# US_EPS_BR.net
KiCad netlist of a schematic drawn in Altium Designer
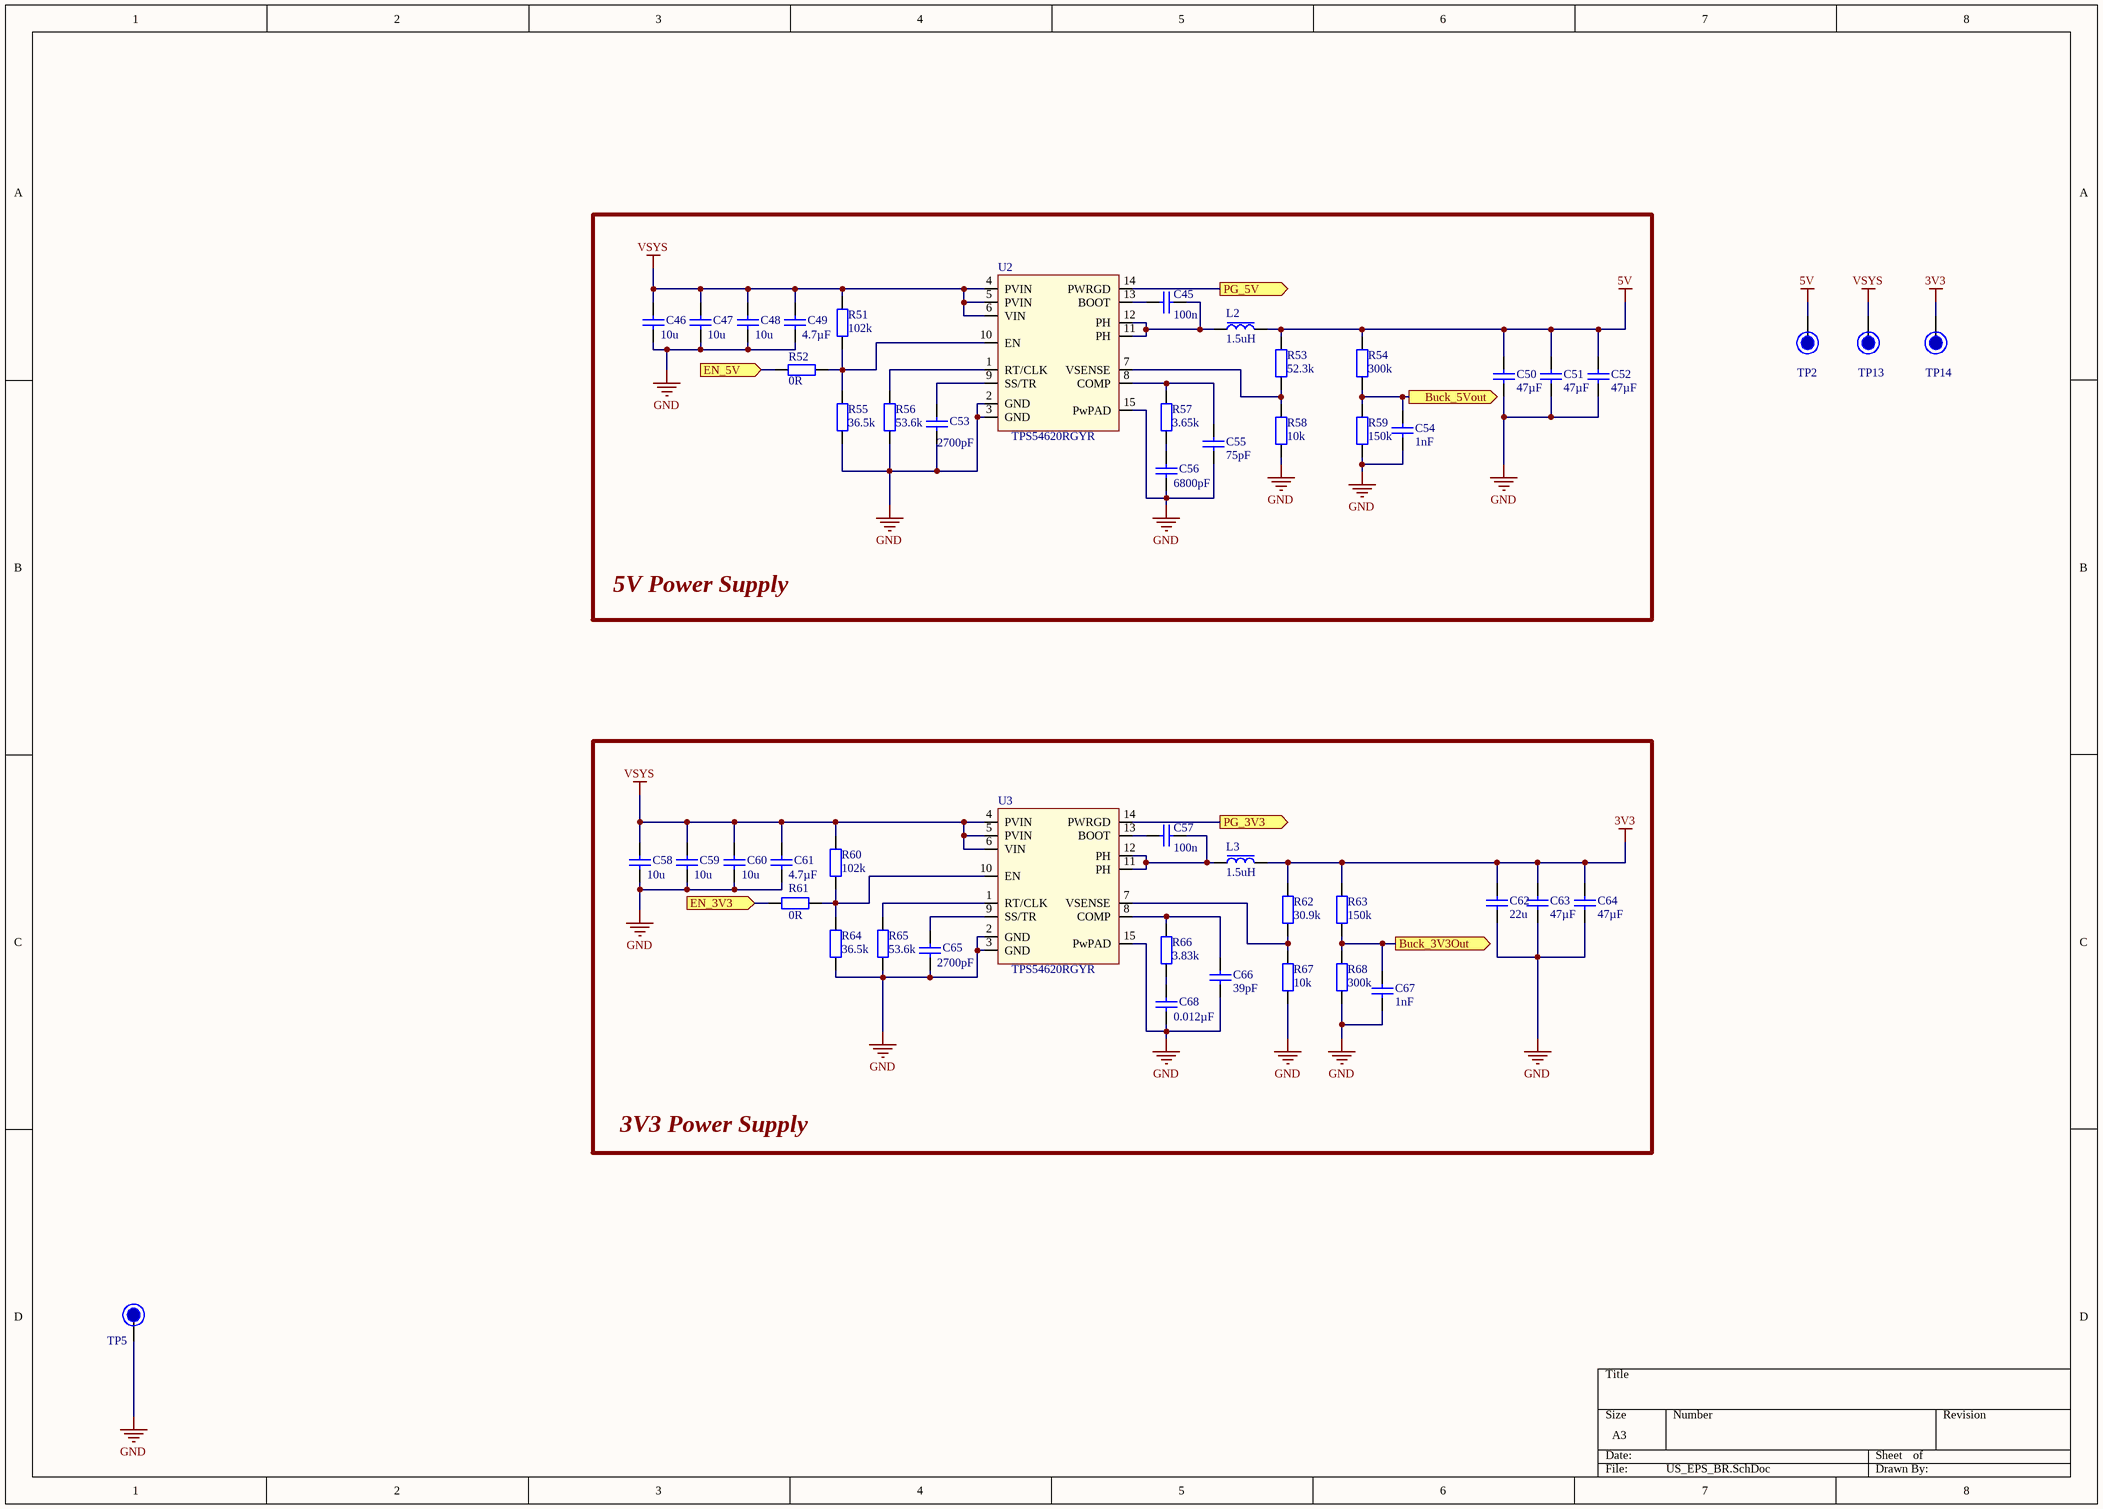
[diagram p0: US_EPS_BR.SchDoc]

(export (version "E")
  (design (tool "Eeschema 10.0.6"))
  (components
    (comp (ref "C45")
      (value "100n")
      (footprint "C0603_IPC_HD")
      (description "CAP CER 0.1UF 16V X7R 0603")
      (fields
        (field (name "MANUFACTURER") "Samsung Electro-Mechanics")
        (field (name "MANUFACTURER PART NUMBER") "CL10B104KO8NNNC")
      )
      (libsource (lib "alfasat_lib") (part "CL10B104KO8NNNC"))
    )
    (comp (ref "C46")
      (value "10u")
      (footprint "C0805_IPC_HD")
      (description "CAP CER 10UF 16V X7R 0805")
      (fields
        (field (name "MANUFACTURER") "Samsung Electro-Mechanics")
        (field (name "MANUFACTURER PART NUMBER") "CL21B106KOQNNNG")
      )
      (libsource (lib "alfasat_lib") (part "CL21B106KOQNNNG"))
    )
    (comp (ref "C47")
      (value "10u")
      (footprint "C0805_IPC_HD")
      (description "CAP CER 10UF 16V X7R 0805")
      (fields
        (field (name "MANUFACTURER") "Samsung Electro-Mechanics")
        (field (name "MANUFACTURER PART NUMBER") "CL21B106KOQNNNG")
      )
      (libsource (lib "alfasat_lib") (part "CL21B106KOQNNNG"))
    )
    (comp (ref "C48")
      (value "10u")
      (footprint "C0805_IPC_HD")
      (description "CAP CER 10UF 16V X7R 0805")
      (fields
        (field (name "MANUFACTURER") "Samsung Electro-Mechanics")
        (field (name "MANUFACTURER PART NUMBER") "CL21B106KOQNNNG")
      )
      (libsource (lib "alfasat_lib") (part "CL21B106KOQNNNG"))
    )
    (comp (ref "C49")
      (value "4.7µF")
      (footprint "C0603_IPC_MD")
      (description "4.7µF ±10% 10V Ceramic Capacitor X5R 0603 (1608 Metric)")
      (fields
        (field (name "MANUFACTURER") "Samsung Electro-Mechanics")
        (field (name "MANUFACTURER PART NUMBER") "CL10A475KP8NNNC")
      )
      (libsource (lib "alfasat_lib_eps") (part "CL0603_4.7uF_10V"))
    )
    (comp (ref "C50")
      (value "47µF")
      (footprint "C1206_IPC_HD")
      (description "CAP CER 47UF 10V X5R 1206")
      (fields
        (field (name "MANUFACTURER") "Samsung Electro-Mechanics")
        (field (name "MANUFACTURER PART NUMBER") "CL31A476MPHNNNE")
      )
      (libsource (lib "alfasat_lib_eps") (part "CL1206_47uF_10V"))
    )
    (comp (ref "C51")
      (value "47µF")
      (footprint "C1206_IPC_HD")
      (description "CAP CER 47UF 10V X5R 1206")
      (fields
        (field (name "MANUFACTURER") "Samsung Electro-Mechanics")
        (field (name "MANUFACTURER PART NUMBER") "CL31A476MPHNNNE")
      )
      (libsource (lib "alfasat_lib_eps") (part "CL1206_47uF_10V"))
    )
    (comp (ref "C52")
      (value "47µF")
      (footprint "C1206_IPC_HD")
      (description "CAP CER 47UF 10V X5R 1206")
      (fields
        (field (name "MANUFACTURER") "Samsung Electro-Mechanics")
        (field (name "MANUFACTURER PART NUMBER") "CL31A476MPHNNNE")
      )
      (libsource (lib "alfasat_lib_eps") (part "CL1206_47uF_10V"))
    )
    (comp (ref "C53")
      (value "2700pF")
      (footprint "C0603_IPC_HD")
      (description "CAP CER 2700PF 50V X7R 0603")
      (fields
        (field (name "MANUFACTURER") "Yageo")
        (field (name "MANUFACTURER PART NUMBER") "CC0603KRX7R9BB272")
      )
      (libsource (lib "alfasat_lib_eps") (part "CL0603_2700pF_50V"))
    )
    (comp (ref "C54")
      (value "1nF")
      (footprint "C0603_IPC_HD")
      (description "CAP CER 1000PF 50V X7R 0603")
      (fields
        (field (name "MANUFACTURER") "Samsung Electro-Mechanics")
        (field (name "MANUFACTURER PART NUMBER") "CL10B102KB8NNNC")
      )
      (libsource (lib "alfasat_lib_eps") (part "CL0603_1nF_0603"))
    )
    (comp (ref "C55")
      (value "75pF")
      (footprint "C0603_IPC_HD")
      (description "CAP CER 75PF 50V C0G/NP0 0603")
      (fields
        (field (name "MANUFACTURER") "Samsung Electro-Mechanics")
        (field (name "MANUFACTURER PART NUMBER") "CL10C750JB8NNNC")
      )
      (libsource (lib "alfasat_lib_eps") (part "C0603_75pF_50V"))
    )
    (comp (ref "C56")
      (value "6800pF")
      (footprint "C0603_IPC_HD")
      (description "CAP CER 6800PF 50V X7R 0603")
      (fields
        (field (name "MANUFACTURER") "TDK Corporation")
        (field (name "MANUFACTURER PART NUMBER") "C1608X7R1H682M")
      )
      (libsource (lib "alfasat_lib_eps") (part "CL0603_6.8nF_50V"))
    )
    (comp (ref "C57")
      (value "100n")
      (footprint "C0603_IPC_HD")
      (description "CAP CER 0.1UF 16V X7R 0603")
      (fields
        (field (name "MANUFACTURER") "Samsung Electro-Mechanics")
        (field (name "MANUFACTURER PART NUMBER") "CL10B104KO8NNNC")
      )
      (libsource (lib "alfasat_lib") (part "CL10B104KO8NNNC"))
    )
    (comp (ref "C58")
      (value "10u")
      (footprint "C0805_IPC_HD")
      (description "CAP CER 10UF 16V X7R 0805")
      (fields
        (field (name "MANUFACTURER") "Samsung Electro-Mechanics")
        (field (name "MANUFACTURER PART NUMBER") "CL21B106KOQNNNG")
      )
      (libsource (lib "alfasat_lib") (part "CL21B106KOQNNNG"))
    )
    (comp (ref "C59")
      (value "10u")
      (footprint "C0805_IPC_HD")
      (description "CAP CER 10UF 16V X7R 0805")
      (fields
        (field (name "MANUFACTURER") "Samsung Electro-Mechanics")
        (field (name "MANUFACTURER PART NUMBER") "CL21B106KOQNNNG")
      )
      (libsource (lib "alfasat_lib") (part "CL21B106KOQNNNG"))
    )
    (comp (ref "C60")
      (value "10u")
      (footprint "C0805_IPC_HD")
      (description "CAP CER 10UF 16V X7R 0805")
      (fields
        (field (name "MANUFACTURER") "Samsung Electro-Mechanics")
        (field (name "MANUFACTURER PART NUMBER") "CL21B106KOQNNNG")
      )
      (libsource (lib "alfasat_lib") (part "CL21B106KOQNNNG"))
    )
    (comp (ref "C61")
      (value "4.7µF")
      (footprint "C0603_IPC_MD")
      (description "4.7µF ±10% 10V Ceramic Capacitor X5R 0603 (1608 Metric)")
      (fields
        (field (name "MANUFACTURER") "Samsung Electro-Mechanics")
        (field (name "MANUFACTURER PART NUMBER") "CL10A475KP8NNNC")
      )
      (libsource (lib "alfasat_lib_eps") (part "CL0603_4.7uF_10V"))
    )
    (comp (ref "C62")
      (value "22u")
      (footprint "C0805_IPC_HD")
      (description "CAP CER 22UF 16V X5R 0805")
      (fields
        (field (name "MANUFACTURER") "Samsung Electro-Mechanics")
        (field (name "MANUFACTURER PART NUMBER") "CL21A226MOCLRNC")
      )
      (libsource (lib "alfasat_lib") (part "CL21A226MOCLRNC"))
    )
    (comp (ref "C63")
      (value "47µF")
      (footprint "C1206_IPC_HD")
      (description "CAP CER 47UF 10V X5R 1206")
      (fields
        (field (name "MANUFACTURER") "Samsung Electro-Mechanics")
        (field (name "MANUFACTURER PART NUMBER") "CL31A476MPHNNNE")
      )
      (libsource (lib "alfasat_lib_eps") (part "CL1206_47uF_10V"))
    )
    (comp (ref "C64")
      (value "47µF")
      (footprint "C1206_IPC_HD")
      (description "CAP CER 47UF 10V X5R 1206")
      (fields
        (field (name "MANUFACTURER") "Samsung Electro-Mechanics")
        (field (name "MANUFACTURER PART NUMBER") "CL31A476MPHNNNE")
      )
      (libsource (lib "alfasat_lib_eps") (part "CL1206_47uF_10V"))
    )
    (comp (ref "C65")
      (value "2700pF")
      (footprint "C0603_IPC_HD")
      (description "CAP CER 2700PF 50V X7R 0603")
      (fields
        (field (name "MANUFACTURER") "Yageo")
        (field (name "MANUFACTURER PART NUMBER") "CC0603KRX7R9BB272")
      )
      (libsource (lib "alfasat_lib_eps") (part "CL0603_2700pF_50V"))
    )
    (comp (ref "C66")
      (value "39pF")
      (footprint "C0603_IPC_HD")
      (description "CAP CER 39PF 50V C0G/NP0 0603")
      (fields
        (field (name "MANUFACTURER") "Samsung Electro-Mechanics")
        (field (name "MANUFACTURER PART NUMBER") "CL10C390JB8NNNC")
      )
      (libsource (lib "alfasat_lib_eps") (part "CL0603_39pF_50V"))
    )
    (comp (ref "C67")
      (value "1nF")
      (footprint "C0603_IPC_HD")
      (description "CAP CER 1000PF 50V X7R 0603")
      (fields
        (field (name "MANUFACTURER") "Samsung Electro-Mechanics")
        (field (name "MANUFACTURER PART NUMBER") "CL10B102KB8NNNC")
      )
      (libsource (lib "alfasat_lib_eps") (part "CL0603_1nF_0603"))
    )
    (comp (ref "C68")
      (value "0.012µF")
      (footprint "C0603_IPC_HD")
      (description "CAP CER 0.012UF 25V C0G/NP0 0603")
      (fields
        (field (name "MANUFACTURER") "KEMET")
        (field (name "MANUFACTURER PART NUMBER") "C0603C123J3GACTU")
      )
      (libsource (lib "alfasat_lib_eps") (part "C0603_12nF_25V"))
    )
    (comp (ref "L2")
      (value "1.5uH")
      (footprint "INDP8687X40N-(VLP8040 )")
      (description "FIXED IND 1.5UH 6.7A 13 MOHM SMD")
      (fields
        (field (name "MANUFACTURER") "TDK Corporation")
        (field (name "MANUFACTURER PART NUMBER") "VLP8040T-1R5N")
      )
      (libsource (lib "alfasat_lib_eps") (part "1.5µH Shielded Wirewound Inductor 6.7A 13mOhm Max Nonstandard"))
    )
    (comp (ref "L3")
      (value "1.5uH")
      (footprint "INDP8687X40N-(VLP8040 )")
      (description "FIXED IND 1.5UH 6.7A 13 MOHM SMD")
      (fields
        (field (name "MANUFACTURER") "TDK Corporation")
        (field (name "MANUFACTURER PART NUMBER") "VLP8040T-1R5N")
      )
      (libsource (lib "alfasat_lib_eps") (part "1.5µH Shielded Wirewound Inductor 6.7A 13mOhm Max Nonstandard"))
    )
    (comp (ref "R51")
      (value "102k")
      (footprint "C0603_IPC_HD")
      (description "RES 102K OHM 1% 1/10W 0603")
      (fields
        (field (name "MANUFACTURER") "KOA Speer Electronics, Inc.")
        (field (name "MANUFACTURER PART NUMBER") "RK73H1JTTD1023F")
      )
      (libsource (lib "alfasat_lib_eps") (part "CR0603-JW-102K"))
    )
    (comp (ref "R52")
      (value "0R")
      (footprint "R0603_IPC_MD")
      (description "RES SMD 0 OHM JUMPER 1/10W 0603")
      (fields
        (field (name "MANUFACTURER") "Bourns Inc.")
        (field (name "MANUFACTURER PART NUMBER") "CR0603-J/-000ELF")
      )
      (libsource (lib "alfasat_lib") (part "CR0603-J/-000ELF"))
    )
    (comp (ref "R53")
      (value "52.3k")
      (footprint "C0603_IPC_HD")
      (description "RES SMD 52.3K OHM 1% 1/10W 0603")
      (fields
        (field (name "MANUFACTURER") "Yageo")
        (field (name "MANUFACTURER PART NUMBER") "RC0603FR-0752K3L")
      )
      (libsource (lib "alfasat_lib_eps") (part "CR0603-JW-52.3k"))
    )
    (comp (ref "R54")
      (value "300k")
      (footprint "R0603_IPC_MD")
      (description "RES SMD 300K OHM 1% 1/10W 0603")
      (fields
        (field (name "MANUFACTURER") "YAGEO")
        (field (name "MANUFACTURER PART NUMBER") "RC0603FR-07300KL")
      )
      (libsource (lib "alfasat_parts_lib") (part "RC0603FR-07300KL"))
    )
    (comp (ref "R55")
      (value "36.5k")
      (footprint "C0603_IPC_HD")
      (description "RES 36.5K OHM 1% 1/10W 0603")
      (fields
        (field (name "MANUFACTURER") "KOA Speer Electronics, Inc.")
        (field (name "MANUFACTURER PART NUMBER") "RK73H1JTTD3652F")
      )
      (libsource (lib "alfasat_lib_eps") (part "CR0603-JW-36.5K"))
    )
    (comp (ref "R56")
      (value "53.6k")
      (footprint "C0603_IPC_HD")
      (description "RES 53.6K OHM 1% 1/10W 0603")
      (fields
        (field (name "MANUFACTURER") "KOA Speer Electronics, Inc.")
        (field (name "MANUFACTURER PART NUMBER") "RK73H1JTTD5362F")
      )
      (libsource (lib "alfasat_lib_eps") (part "CR0603-JW-53.6k"))
    )
    (comp (ref "R57")
      (value "3.65k")
      (footprint "C0603_IPC_HD")
      (description "RES SMD 3.65K OHM 1% 1/10W 0603")
      (fields
        (field (name "MANUFACTURER") "Yageo")
        (field (name "MANUFACTURER PART NUMBER") "RC0603FR-073K65L")
      )
      (libsource (lib "alfasat_lib_eps") (part "CR0603-JW-3.65k"))
    )
    (comp (ref "R58")
      (value "10k")
      (footprint "alfasat_lib_eps:C0603_IPC_HD")
      (description "RES 10K OHM 1% 1/10W 0603")
      (fields
        (field (name "MANUFACTURER") "Stackpole Electronics Inc")
        (field (name "MANUFACTURER PART NUMBER") "RMCF0603FT10K0")
      )
      (libsource (lib "alfasat_lib_eps") (part "CR0603-JW-10к"))
    )
    (comp (ref "R59")
      (value "150k")
      (footprint "R0603_IPC_MD")
      (description "RES SMD 150K OHM 1% 1/10W 0603")
      (fields
        (field (name "MANUFACTURER") "YAGEO")
        (field (name "MANUFACTURER PART NUMBER") "RC0603FR-07150KL")
      )
      (libsource (lib "alfasat_parts_lib") (part "RC0603FR-07150KL"))
    )
    (comp (ref "R60")
      (value "102k")
      (footprint "C0603_IPC_HD")
      (description "RES 102K OHM 1% 1/10W 0603")
      (fields
        (field (name "MANUFACTURER") "KOA Speer Electronics, Inc.")
        (field (name "MANUFACTURER PART NUMBER") "RK73H1JTTD1023F")
      )
      (libsource (lib "alfasat_lib_eps") (part "CR0603-JW-102K"))
    )
    (comp (ref "R61")
      (value "0R")
      (footprint "R0603_IPC_MD")
      (description "RES SMD 0 OHM JUMPER 1/10W 0603")
      (fields
        (field (name "MANUFACTURER") "Bourns Inc.")
        (field (name "MANUFACTURER PART NUMBER") "CR0603-J/-000ELF")
      )
      (libsource (lib "alfasat_lib") (part "CR0603-J/-000ELF"))
    )
    (comp (ref "R62")
      (value "30.9k")
      (footprint "C0603_IPC_HD")
      (description "RES SMD 30.9K OHM 1% 1/10W 0603")
      (fields
        (field (name "MANUFACTURER") "Yageo")
        (field (name "MANUFACTURER PART NUMBER") "RC0603FR-0730K9L")
      )
      (libsource (lib "alfasat_lib_eps") (part "CR0603-JW-30.9k"))
    )
    (comp (ref "R63")
      (value "150k")
      (footprint "R0603_IPC_MD")
      (description "RES SMD 150K OHM 1% 1/10W 0603")
      (fields
        (field (name "MANUFACTURER") "YAGEO")
        (field (name "MANUFACTURER PART NUMBER") "RC0603FR-07150KL")
      )
      (libsource (lib "alfasat_parts_lib") (part "RC0603FR-07150KL"))
    )
    (comp (ref "R64")
      (value "36.5k")
      (footprint "C0603_IPC_HD")
      (description "RES 36.5K OHM 1% 1/10W 0603")
      (fields
        (field (name "MANUFACTURER") "KOA Speer Electronics, Inc.")
        (field (name "MANUFACTURER PART NUMBER") "RK73H1JTTD3652F")
      )
      (libsource (lib "alfasat_lib_eps") (part "CR0603-JW-36.5K"))
    )
    (comp (ref "R65")
      (value "53.6k")
      (footprint "C0603_IPC_HD")
      (description "RES 53.6K OHM 1% 1/10W 0603")
      (fields
        (field (name "MANUFACTURER") "KOA Speer Electronics, Inc.")
        (field (name "MANUFACTURER PART NUMBER") "RK73H1JTTD5362F")
      )
      (libsource (lib "alfasat_lib_eps") (part "CR0603-JW-53.6k"))
    )
    (comp (ref "R66")
      (value "3.83k")
      (footprint "C0603_IPC_HD")
      (description "RES SMD 3.83K OHM 1% 1/10W 0603")
      (fields
        (field (name "MANUFACTURER") "Yageo")
        (field (name "MANUFACTURER PART NUMBER") "RC0603FR-073K83L")
      )
      (libsource (lib "alfasat_lib_eps") (part "CR0603-JW-3.83k"))
    )
    (comp (ref "R67")
      (value "10k")
      (footprint "C0603_IPC_HD")
      (description "RES 10K OHM 1% 1/10W 0603")
      (fields
        (field (name "MANUFACTURER") "Stackpole Electronics Inc")
        (field (name "MANUFACTURER PART NUMBER") "RMCF0603FT10K0")
      )
      (libsource (lib "alfasat_lib_eps") (part "CR0603-JW-10k"))
    )
    (comp (ref "R68")
      (value "300k")
      (footprint "R0603_IPC_MD")
      (description "RES SMD 300K OHM 1% 1/10W 0603")
      (fields
        (field (name "MANUFACTURER") "YAGEO")
        (field (name "MANUFACTURER PART NUMBER") "RC0603FR-07300KL")
      )
      (libsource (lib "alfasat_parts_lib") (part "RC0603FR-07300KL"))
    )
    (comp (ref "TP2")
      (value "Test Point")
      (footprint "TestPoint_1M5")
      (libsource (lib "alfasat_lib") (part "TP"))
    )
    (comp (ref "TP5")
      (value "Test Point")
      (footprint "TestPoint_1M5")
      (libsource (lib "alfasat_lib") (part "TP"))
    )
    (comp (ref "TP13")
      (value "Test Point")
      (footprint "TestPoint_1M5")
      (libsource (lib "alfasat_lib") (part "TP"))
    )
    (comp (ref "TP14")
      (value "Test Point")
      (footprint "TestPoint_1M5")
      (libsource (lib "alfasat_lib") (part "TP"))
    )
    (comp (ref "U2")
      (value "TPS54620RGYR")
      (footprint "14-VFQFN-(TPS54620RGYR)")
      (description "IC REG BUCK ADJUSTABLE 6A 14VQFN")
      (fields (field (name "MANUFACTURER") "Texas Instruments"))
      (libsource (lib "alfasat_lib_eps") (part "TPS54620RGYR"))
    )
    (comp (ref "U3")
      (value "TPS54620RGYR")
      (footprint "14-VFQFN-(TPS54620RGYR)")
      (description "IC REG BUCK ADJUSTABLE 6A 14VQFN")
      (fields (field (name "MANUFACTURER") "Texas Instruments"))
      (libsource (lib "alfasat_lib_eps") (part "TPS54620RGYR"))
    )
  )
  (nets
    (net (code "1") (name "/Buck_3V3Out") (class "Default")
      (node (ref "C67") (pin "2") (pinfunction "2_2") (pintype "passive"))
      (node (ref "R63") (pin "1") (pinfunction "1_1") (pintype "passive"))
      (node (ref "R68") (pin "2") (pinfunction "2_2") (pintype "passive"))
    )
    (net (code "2") (name "/Buck_5Vout") (class "Default")
      (node (ref "C54") (pin "2") (pinfunction "2_2") (pintype "passive"))
      (node (ref "R54") (pin "1") (pinfunction "1_1") (pintype "passive"))
      (node (ref "R59") (pin "2") (pinfunction "2_2") (pintype "passive"))
    )
    (net (code "3") (name "/EN_3V3") (class "Default")
      (node (ref "R61") (pin "2") (pinfunction "2_2") (pintype "passive"))
    )
    (net (code "4") (name "/EN_5V") (class "Default")
      (node (ref "R52") (pin "2") (pinfunction "2_2") (pintype "passive"))
    )
    (net (code "5") (name "/PG_3V3") (class "Default")
      (node (ref "U3") (pin "14") (pinfunction "PWRGD_14") (pintype "passive"))
    )
    (net (code "6") (name "/PG_5V") (class "Default")
      (node (ref "U2") (pin "14") (pinfunction "PWRGD_14") (pintype "passive"))
    )
    (net (code "7") (name "3V3") (class "Default")
      (node (ref "C62") (pin "2") (pinfunction "2_2") (pintype "passive"))
      (node (ref "C63") (pin "2") (pinfunction "2_2") (pintype "passive"))
      (node (ref "C64") (pin "2") (pinfunction "2_2") (pintype "passive"))
      (node (ref "L3") (pin "2") (pinfunction "2_2") (pintype "passive"))
      (node (ref "R62") (pin "2") (pinfunction "2_2") (pintype "passive"))
      (node (ref "R63") (pin "2") (pinfunction "2_2") (pintype "passive"))
      (node (ref "TP14") (pin "0") (pinfunction "0_0") (pintype "passive"))
    )
    (net (code "8") (name "5V") (class "Default")
      (node (ref "C50") (pin "2") (pinfunction "2_2") (pintype "passive"))
      (node (ref "C51") (pin "2") (pinfunction "2_2") (pintype "passive"))
      (node (ref "C52") (pin "2") (pinfunction "2_2") (pintype "passive"))
      (node (ref "L2") (pin "2") (pinfunction "2_2") (pintype "passive"))
      (node (ref "R53") (pin "2") (pinfunction "2_2") (pintype "passive"))
      (node (ref "R54") (pin "2") (pinfunction "2_2") (pintype "passive"))
      (node (ref "TP2") (pin "0") (pinfunction "0_0") (pintype "passive"))
    )
    (net (code "9") (name "GND") (class "Default")
      (node (ref "C46") (pin "1") (pinfunction "1_1") (pintype "passive"))
      (node (ref "C47") (pin "1") (pinfunction "1_1") (pintype "passive"))
      (node (ref "C48") (pin "1") (pinfunction "1_1") (pintype "passive"))
      (node (ref "C49") (pin "1") (pinfunction "1_1") (pintype "passive"))
      (node (ref "C50") (pin "1") (pinfunction "1_1") (pintype "passive"))
      (node (ref "C51") (pin "1") (pinfunction "1_1") (pintype "passive"))
      (node (ref "C52") (pin "1") (pinfunction "1_1") (pintype "passive"))
      (node (ref "C53") (pin "1") (pinfunction "1_1") (pintype "passive"))
      (node (ref "C54") (pin "1") (pinfunction "1_1") (pintype "passive"))
      (node (ref "C55") (pin "1") (pinfunction "1_1") (pintype "passive"))
      (node (ref "C56") (pin "1") (pinfunction "1_1") (pintype "passive"))
      (node (ref "C58") (pin "1") (pinfunction "1_1") (pintype "passive"))
      (node (ref "C59") (pin "1") (pinfunction "1_1") (pintype "passive"))
      (node (ref "C60") (pin "1") (pinfunction "1_1") (pintype "passive"))
      (node (ref "C61") (pin "1") (pinfunction "1_1") (pintype "passive"))
      (node (ref "C62") (pin "1") (pinfunction "1_1") (pintype "passive"))
      (node (ref "C63") (pin "1") (pinfunction "1_1") (pintype "passive"))
      (node (ref "C64") (pin "1") (pinfunction "1_1") (pintype "passive"))
      (node (ref "C65") (pin "1") (pinfunction "1_1") (pintype "passive"))
      (node (ref "C66") (pin "1") (pinfunction "1_1") (pintype "passive"))
      (node (ref "C67") (pin "1") (pinfunction "1_1") (pintype "passive"))
      (node (ref "C68") (pin "1") (pinfunction "1_1") (pintype "passive"))
      (node (ref "R55") (pin "1") (pinfunction "1_1") (pintype "passive"))
      (node (ref "R56") (pin "1") (pinfunction "1_1") (pintype "passive"))
      (node (ref "R58") (pin "1") (pinfunction "1_1") (pintype "passive"))
      (node (ref "R59") (pin "1") (pinfunction "1_1") (pintype "passive"))
      (node (ref "R64") (pin "1") (pinfunction "1_1") (pintype "passive"))
      (node (ref "R65") (pin "1") (pinfunction "1_1") (pintype "passive"))
      (node (ref "R67") (pin "1") (pinfunction "1_1") (pintype "passive"))
      (node (ref "R68") (pin "1") (pinfunction "1_1") (pintype "passive"))
      (node (ref "TP5") (pin "0") (pinfunction "0_0") (pintype "passive"))
      (node (ref "U2") (pin "15") (pinfunction "PwPAD_15") (pintype "passive"))
      (node (ref "U2") (pin "2") (pinfunction "GND_2") (pintype "passive"))
      (node (ref "U2") (pin "3") (pinfunction "GND_3") (pintype "passive"))
      (node (ref "U3") (pin "15") (pinfunction "PwPAD_15") (pintype "passive"))
      (node (ref "U3") (pin "2") (pinfunction "GND_2") (pintype "passive"))
      (node (ref "U3") (pin "3") (pinfunction "GND_3") (pintype "passive"))
    )
    (net (code "10") (name "Net-(C45-Pad1)") (class "Default")
      (node (ref "C45") (pin "1") (pinfunction "1_1") (pintype "passive"))
      (node (ref "L2") (pin "1") (pinfunction "1_1") (pintype "passive"))
      (node (ref "U2") (pin "11") (pinfunction "PH_11") (pintype "passive"))
      (node (ref "U2") (pin "12") (pinfunction "PH_12") (pintype "passive"))
    )
    (net (code "11") (name "Net-(C56-Pad2)") (class "Default")
      (node (ref "C56") (pin "2") (pinfunction "2_2") (pintype "passive"))
      (node (ref "R57") (pin "1") (pinfunction "1_1") (pintype "passive"))
    )
    (net (code "12") (name "Net-(C57-Pad1)") (class "Default")
      (node (ref "C57") (pin "1") (pinfunction "1_1") (pintype "passive"))
      (node (ref "L3") (pin "1") (pinfunction "1_1") (pintype "passive"))
      (node (ref "U3") (pin "11") (pinfunction "PH_11") (pintype "passive"))
      (node (ref "U3") (pin "12") (pinfunction "PH_12") (pintype "passive"))
    )
    (net (code "13") (name "Net-(C68-Pad2)") (class "Default")
      (node (ref "C68") (pin "2") (pinfunction "2_2") (pintype "passive"))
      (node (ref "R66") (pin "1") (pinfunction "1_1") (pintype "passive"))
    )
    (net (code "14") (name "Net-(U2-BOOT)") (class "Default")
      (node (ref "C45") (pin "2") (pinfunction "2_2") (pintype "passive"))
      (node (ref "U2") (pin "13") (pinfunction "BOOT_13") (pintype "passive"))
    )
    (net (code "15") (name "Net-(U2-COMP)") (class "Default")
      (node (ref "C55") (pin "2") (pinfunction "2_2") (pintype "passive"))
      (node (ref "R57") (pin "2") (pinfunction "2_2") (pintype "passive"))
      (node (ref "U2") (pin "8") (pinfunction "COMP_8") (pintype "passive"))
    )
    (net (code "16") (name "Net-(U2-EN)") (class "Default")
      (node (ref "R51") (pin "1") (pinfunction "1_1") (pintype "passive"))
      (node (ref "R52") (pin "1") (pinfunction "1_1") (pintype "passive"))
      (node (ref "R55") (pin "2") (pinfunction "2_2") (pintype "passive"))
      (node (ref "U2") (pin "10") (pinfunction "EN_10") (pintype "passive"))
    )
    (net (code "17") (name "Net-(U2-RT{slash}CLK)") (class "Default")
      (node (ref "R56") (pin "2") (pinfunction "2_2") (pintype "passive"))
      (node (ref "U2") (pin "1") (pinfunction "RT/CLK_1") (pintype "passive"))
    )
    (net (code "18") (name "Net-(U2-SS{slash}TR)") (class "Default")
      (node (ref "C53") (pin "2") (pinfunction "2_2") (pintype "passive"))
      (node (ref "U2") (pin "9") (pinfunction "SS/TR_9") (pintype "passive"))
    )
    (net (code "19") (name "Net-(U2-VSENSE)") (class "Default")
      (node (ref "R53") (pin "1") (pinfunction "1_1") (pintype "passive"))
      (node (ref "R58") (pin "2") (pinfunction "2_2") (pintype "passive"))
      (node (ref "U2") (pin "7") (pinfunction "VSENSE_7") (pintype "passive"))
    )
    (net (code "20") (name "Net-(U3-BOOT)") (class "Default")
      (node (ref "C57") (pin "2") (pinfunction "2_2") (pintype "passive"))
      (node (ref "U3") (pin "13") (pinfunction "BOOT_13") (pintype "passive"))
    )
    (net (code "21") (name "Net-(U3-COMP)") (class "Default")
      (node (ref "C66") (pin "2") (pinfunction "2_2") (pintype "passive"))
      (node (ref "R66") (pin "2") (pinfunction "2_2") (pintype "passive"))
      (node (ref "U3") (pin "8") (pinfunction "COMP_8") (pintype "passive"))
    )
    (net (code "22") (name "Net-(U3-EN)") (class "Default")
      (node (ref "R60") (pin "1") (pinfunction "1_1") (pintype "passive"))
      (node (ref "R61") (pin "1") (pinfunction "1_1") (pintype "passive"))
      (node (ref "R64") (pin "2") (pinfunction "2_2") (pintype "passive"))
      (node (ref "U3") (pin "10") (pinfunction "EN_10") (pintype "passive"))
    )
    (net (code "23") (name "Net-(U3-RT{slash}CLK)") (class "Default")
      (node (ref "R65") (pin "2") (pinfunction "2_2") (pintype "passive"))
      (node (ref "U3") (pin "1") (pinfunction "RT/CLK_1") (pintype "passive"))
    )
    (net (code "24") (name "Net-(U3-SS{slash}TR)") (class "Default")
      (node (ref "C65") (pin "2") (pinfunction "2_2") (pintype "passive"))
      (node (ref "U3") (pin "9") (pinfunction "SS/TR_9") (pintype "passive"))
    )
    (net (code "25") (name "Net-(U3-VSENSE)") (class "Default")
      (node (ref "R62") (pin "1") (pinfunction "1_1") (pintype "passive"))
      (node (ref "R67") (pin "2") (pinfunction "2_2") (pintype "passive"))
      (node (ref "U3") (pin "7") (pinfunction "VSENSE_7") (pintype "passive"))
    )
    (net (code "26") (name "VSYS") (class "Default")
      (node (ref "C46") (pin "2") (pinfunction "2_2") (pintype "passive"))
      (node (ref "C47") (pin "2") (pinfunction "2_2") (pintype "passive"))
      (node (ref "C48") (pin "2") (pinfunction "2_2") (pintype "passive"))
      (node (ref "C49") (pin "2") (pinfunction "2_2") (pintype "passive"))
      (node (ref "C58") (pin "2") (pinfunction "2_2") (pintype "passive"))
      (node (ref "C59") (pin "2") (pinfunction "2_2") (pintype "passive"))
      (node (ref "C60") (pin "2") (pinfunction "2_2") (pintype "passive"))
      (node (ref "C61") (pin "2") (pinfunction "2_2") (pintype "passive"))
      (node (ref "R51") (pin "2") (pinfunction "2_2") (pintype "passive"))
      (node (ref "R60") (pin "2") (pinfunction "2_2") (pintype "passive"))
      (node (ref "TP13") (pin "0") (pinfunction "0_0") (pintype "passive"))
      (node (ref "U2") (pin "4") (pinfunction "PVIN_4") (pintype "passive"))
      (node (ref "U2") (pin "5") (pinfunction "PVIN_5") (pintype "passive"))
      (node (ref "U2") (pin "6") (pinfunction "VIN_6") (pintype "passive"))
      (node (ref "U3") (pin "4") (pinfunction "PVIN_4") (pintype "passive"))
      (node (ref "U3") (pin "5") (pinfunction "PVIN_5") (pintype "passive"))
      (node (ref "U3") (pin "6") (pinfunction "VIN_6") (pintype "passive"))
    )
  )
)
